# 19P_Connector.net
KiCad netlist of a schematic drawn in EAGLE
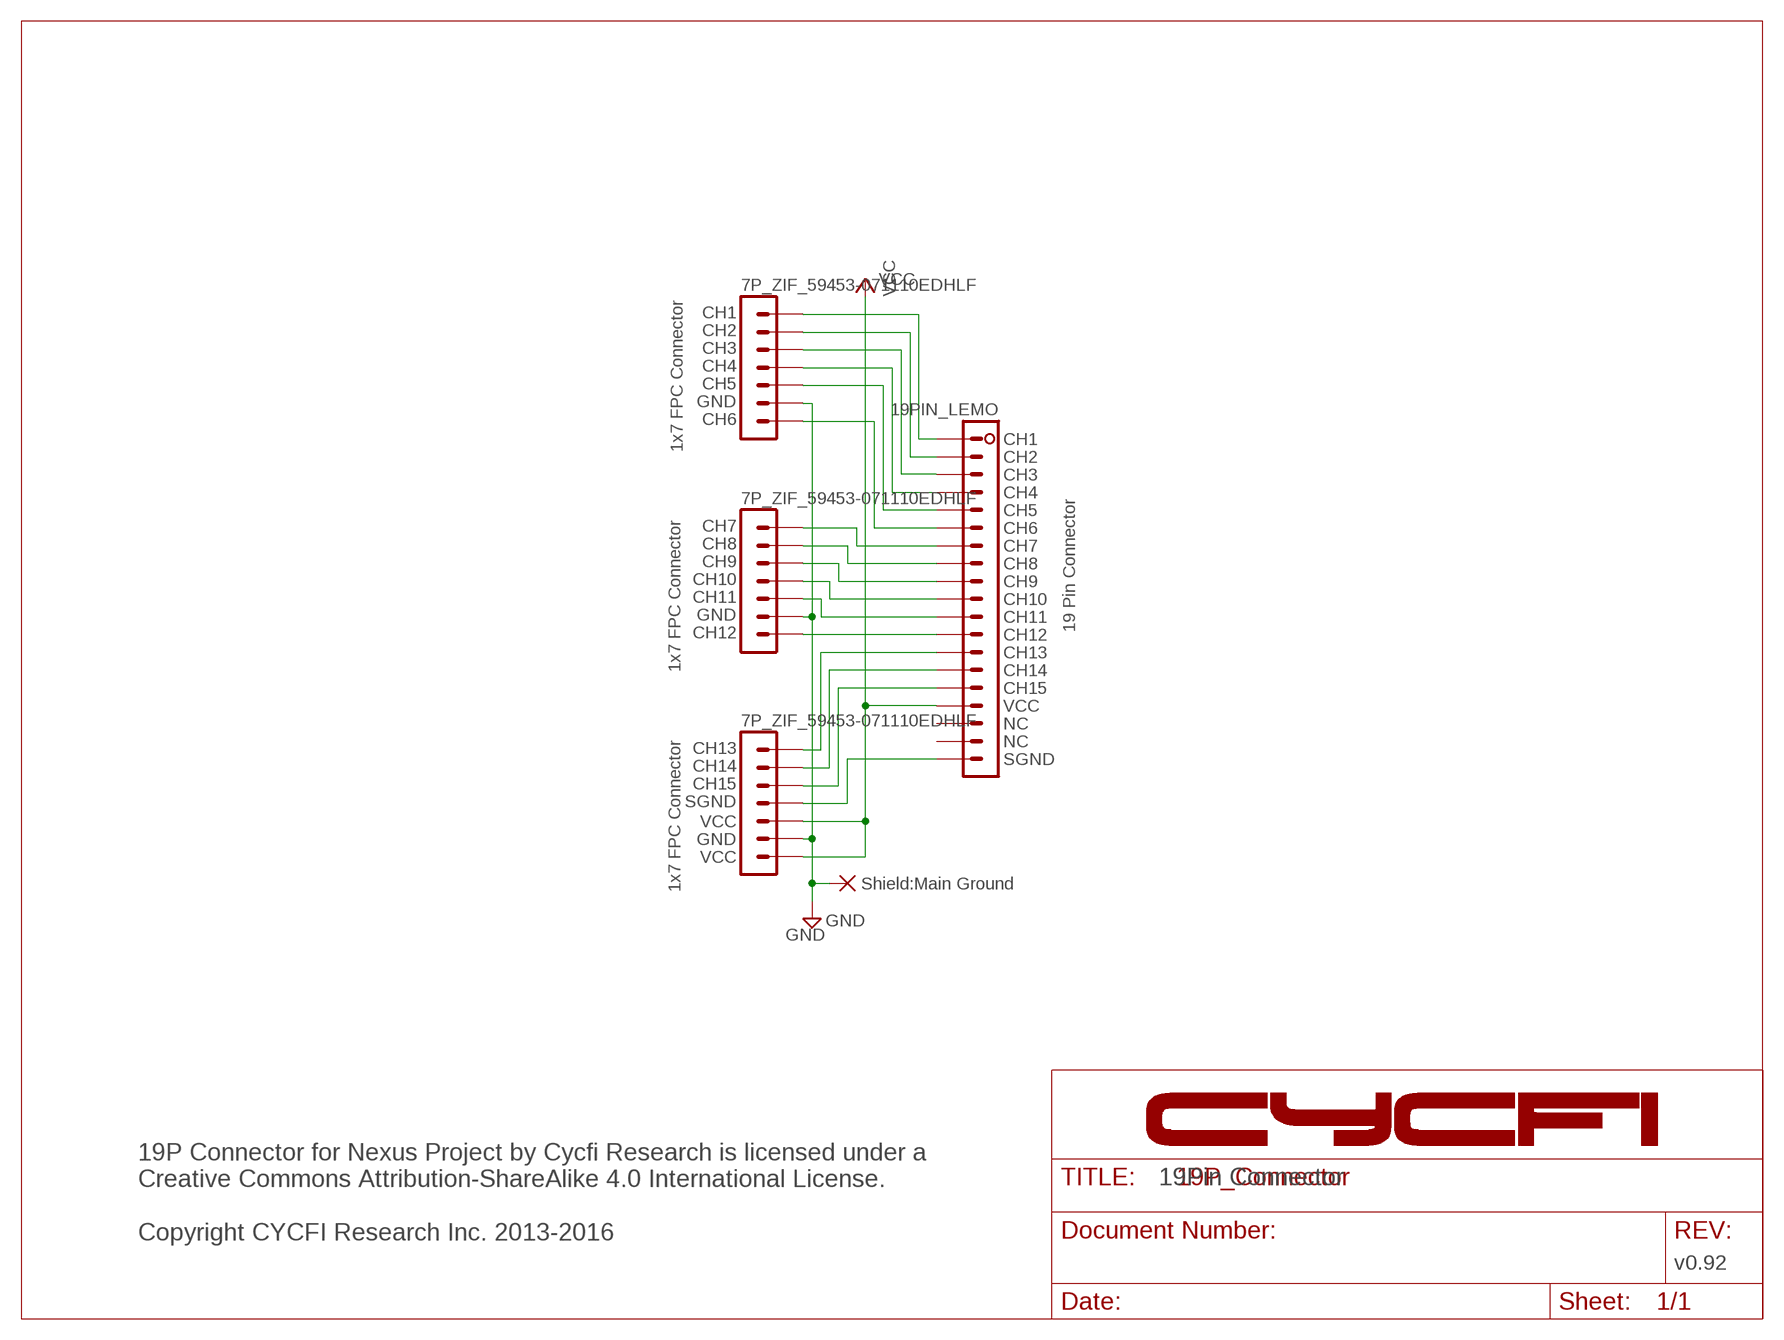
[diagram p0: schematic, sheet 1]

(export (version "E")
  (design (tool "Eeschema 10.0.6"))
  (components
    (comp (ref "C1")
      (value "19PIN_LEMO")
      (footprint "eagle-import:19PIN_LEMO")
      (libsource (lib "eagle-import") (part "19PIN_LEMO"))
    )
    (comp (ref "H1")
      (value "7P_ZIF_59453-071110EDHLF")
      (footprint "eagle-import:7P_ZIF_59453-071110EDHLF")
      (libsource (lib "eagle-import") (part "7P_ZIF_59453-071110EDHLF"))
    )
    (comp (ref "H2")
      (value "7P_ZIF_59453-071110EDHLF")
      (footprint "eagle-import:7P_ZIF_59453-071110EDHLF")
      (libsource (lib "eagle-import") (part "7P_ZIF_59453-071110EDHLF"))
    )
    (comp (ref "H3")
      (value "7P_ZIF_59453-071110EDHLF")
      (footprint "eagle-import:7P_ZIF_59453-071110EDHLF")
      (libsource (lib "eagle-import") (part "7P_ZIF_59453-071110EDHLF"))
    )
    (comp (ref "PAD1")
      (value "1,6/0,8")
      (footprint "eagle-import:1,6_0,8")
      (libsource (lib "eagle-import") (part "1,6/0,8"))
    )
  )
  (nets
    (net (code "1") (name "GND") (class "Default")
      (node (ref "H1") (pin "P$6") (pinfunction "6_P$6") (pintype "passive"))
      (node (ref "H2") (pin "P$6") (pinfunction "6_P$6") (pintype "passive"))
      (node (ref "H3") (pin "P$6") (pinfunction "6_P$6") (pintype "passive"))
      (node (ref "PAD1") (pin "1") (pinfunction "P_1") (pintype "passive"))
    )
    (net (code "2") (name "Net-(C1-1)") (class "Default")
      (node (ref "C1") (pin "P$1") (pinfunction "1_P$1") (pintype "passive"))
      (node (ref "H1") (pin "P$1") (pinfunction "1_P$1") (pintype "passive"))
    )
    (net (code "3") (name "Net-(C1-2)") (class "Default")
      (node (ref "C1") (pin "P$2") (pinfunction "2_P$2") (pintype "passive"))
      (node (ref "H1") (pin "P$2") (pinfunction "2_P$2") (pintype "passive"))
    )
    (net (code "4") (name "Net-(C1-3)") (class "Default")
      (node (ref "C1") (pin "P$3") (pinfunction "3_P$3") (pintype "passive"))
      (node (ref "H1") (pin "P$3") (pinfunction "3_P$3") (pintype "passive"))
    )
    (net (code "5") (name "Net-(C1-4)") (class "Default")
      (node (ref "C1") (pin "P$4") (pinfunction "4_P$4") (pintype "passive"))
      (node (ref "H1") (pin "P$4") (pinfunction "4_P$4") (pintype "passive"))
    )
    (net (code "6") (name "Net-(C1-5)") (class "Default")
      (node (ref "C1") (pin "P$5") (pinfunction "5_P$5") (pintype "passive"))
      (node (ref "H1") (pin "P$5") (pinfunction "5_P$5") (pintype "passive"))
    )
    (net (code "7") (name "Net-(C1-6)") (class "Default")
      (node (ref "C1") (pin "P$6") (pinfunction "6_P$6") (pintype "passive"))
      (node (ref "H1") (pin "P$7") (pinfunction "7_P$7") (pintype "passive"))
    )
    (net (code "8") (name "Net-(C1-7)") (class "Default")
      (node (ref "C1") (pin "P$7") (pinfunction "7_P$7") (pintype "passive"))
      (node (ref "H2") (pin "P$1") (pinfunction "1_P$1") (pintype "passive"))
    )
    (net (code "9") (name "Net-(C1-8)") (class "Default")
      (node (ref "C1") (pin "P$8") (pinfunction "8_P$8") (pintype "passive"))
      (node (ref "H2") (pin "P$2") (pinfunction "2_P$2") (pintype "passive"))
    )
    (net (code "10") (name "Net-(C1-9)") (class "Default")
      (node (ref "C1") (pin "P$9") (pinfunction "9_P$9") (pintype "passive"))
      (node (ref "H2") (pin "P$3") (pinfunction "3_P$3") (pintype "passive"))
    )
    (net (code "11") (name "Net-(C1-10)") (class "Default")
      (node (ref "C1") (pin "P$10") (pinfunction "10_P$10") (pintype "passive"))
      (node (ref "H2") (pin "P$4") (pinfunction "4_P$4") (pintype "passive"))
    )
    (net (code "12") (name "Net-(C1-11)") (class "Default")
      (node (ref "C1") (pin "P$11") (pinfunction "11_P$11") (pintype "passive"))
      (node (ref "H2") (pin "P$5") (pinfunction "5_P$5") (pintype "passive"))
    )
    (net (code "13") (name "Net-(C1-12)") (class "Default")
      (node (ref "C1") (pin "P$12") (pinfunction "12_P$12") (pintype "passive"))
      (node (ref "H2") (pin "P$7") (pinfunction "7_P$7") (pintype "passive"))
    )
    (net (code "14") (name "Net-(C1-13)") (class "Default")
      (node (ref "C1") (pin "P$13") (pinfunction "13_P$13") (pintype "passive"))
      (node (ref "H3") (pin "P$1") (pinfunction "1_P$1") (pintype "passive"))
    )
    (net (code "15") (name "Net-(C1-14)") (class "Default")
      (node (ref "C1") (pin "P$14") (pinfunction "14_P$14") (pintype "passive"))
      (node (ref "H3") (pin "P$2") (pinfunction "2_P$2") (pintype "passive"))
    )
    (net (code "16") (name "Net-(C1-15)") (class "Default")
      (node (ref "C1") (pin "P$15") (pinfunction "15_P$15") (pintype "passive"))
      (node (ref "H3") (pin "P$3") (pinfunction "3_P$3") (pintype "passive"))
    )
    (net (code "17") (name "Net-(C1-19)") (class "Default")
      (node (ref "C1") (pin "P$19") (pinfunction "19_P$19") (pintype "passive"))
      (node (ref "H3") (pin "P$4") (pinfunction "4_P$4") (pintype "passive"))
    )
    (net (code "18") (name "VCC") (class "Default")
      (node (ref "C1") (pin "P$16") (pinfunction "16_P$16") (pintype "passive"))
      (node (ref "H3") (pin "P$5") (pinfunction "5_P$5") (pintype "passive"))
      (node (ref "H3") (pin "P$7") (pinfunction "7_P$7") (pintype "passive"))
    )
    (net (code "19") (name "unconnected-(C1-17-PadP$17)") (class "Default")
      (node (ref "C1") (pin "P$17") (pinfunction "17_P$17") (pintype "passive"))
    )
    (net (code "20") (name "unconnected-(C1-18-PadP$18)") (class "Default")
      (node (ref "C1") (pin "P$18") (pinfunction "18_P$18") (pintype "passive"))
    )
  )
)
